# TCAN1146_PINOUT.net
KiCad netlist of a schematic drawn in Altium Designer
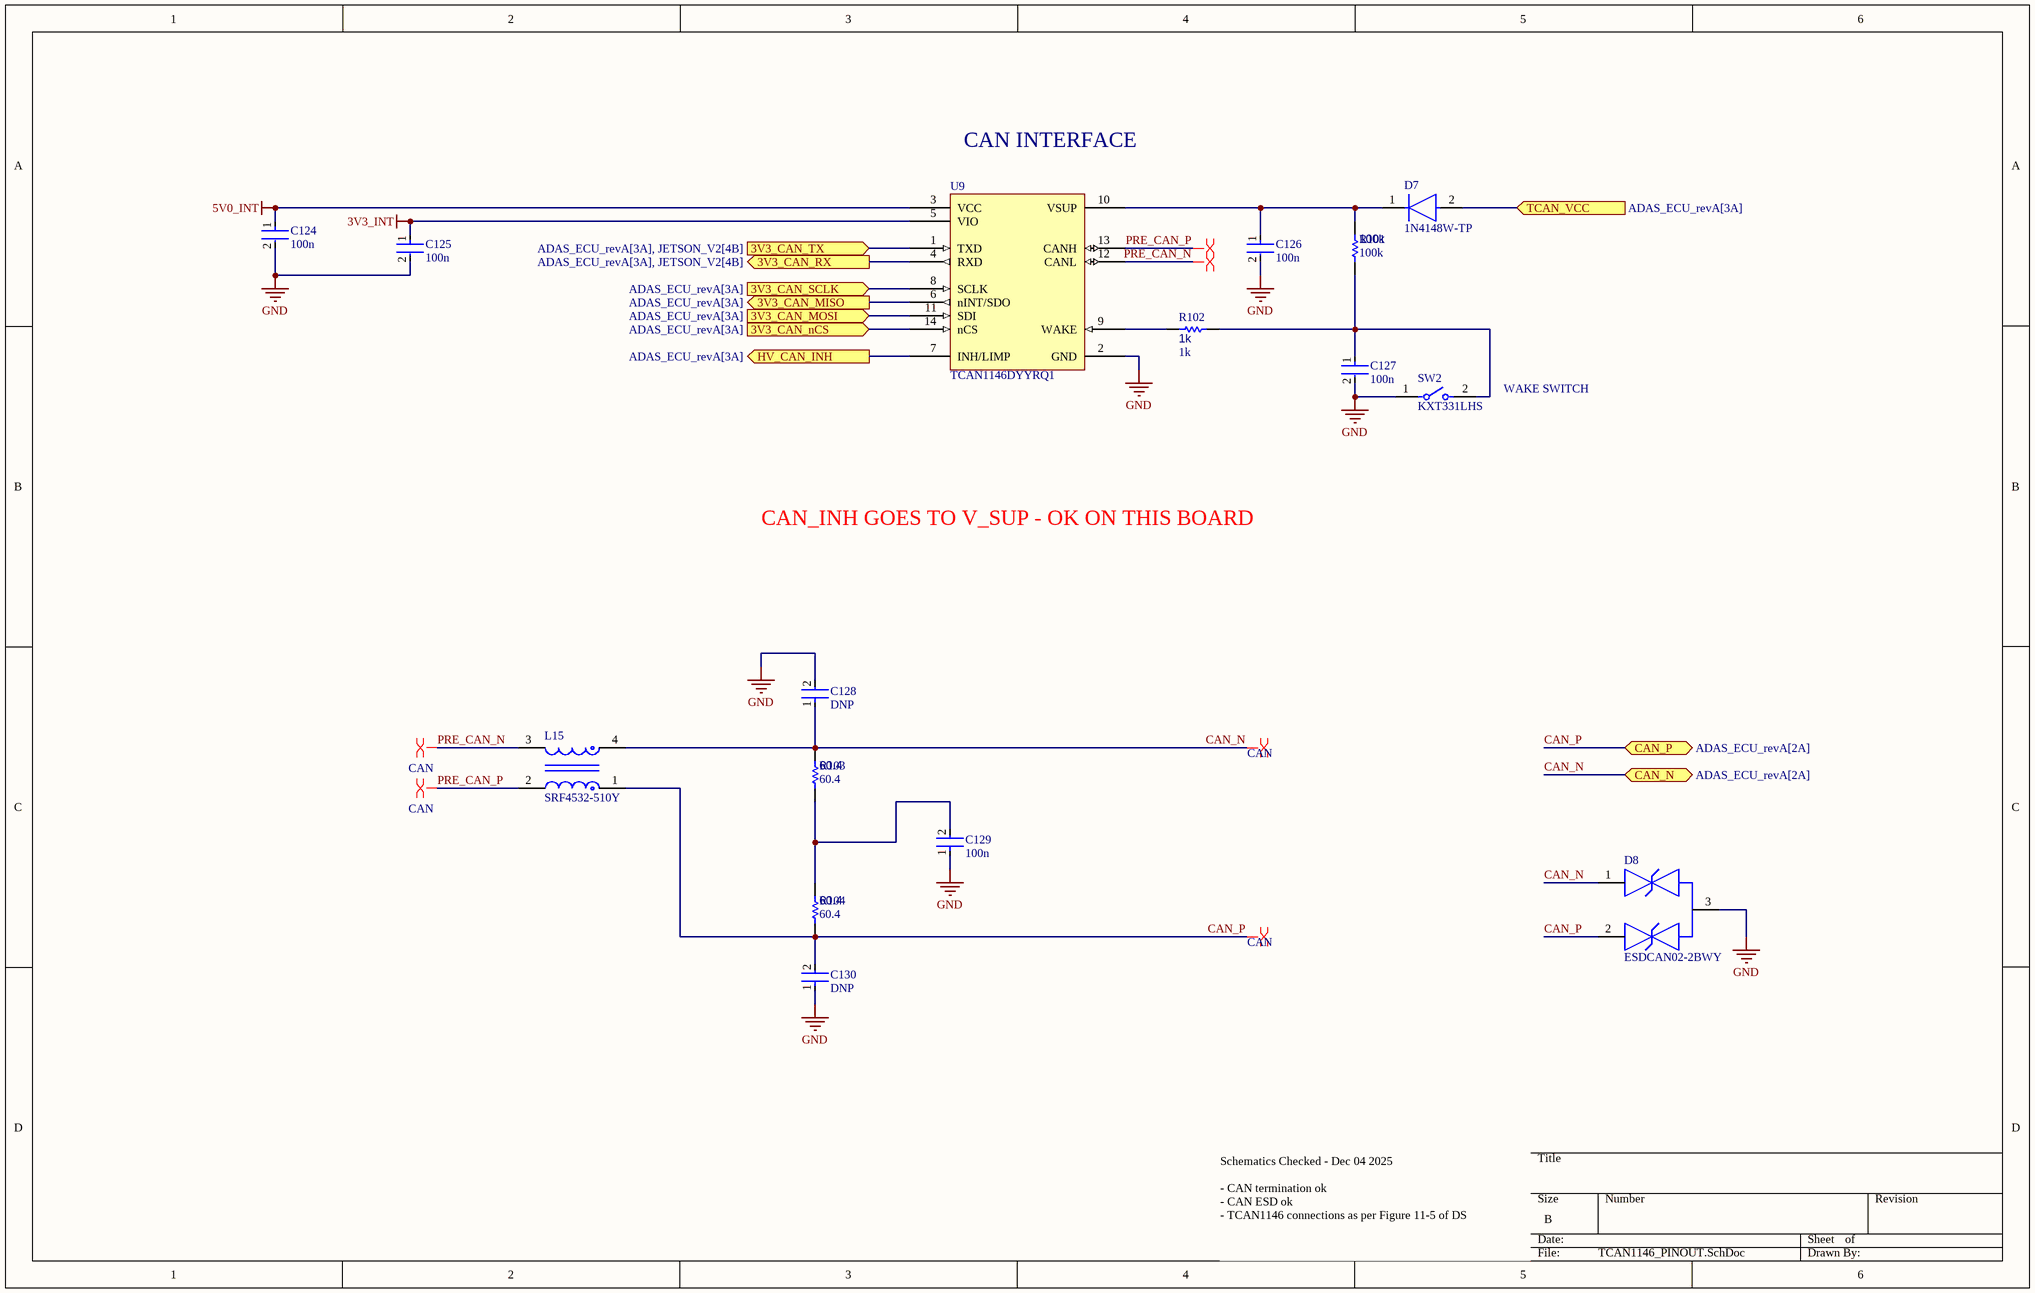
[diagram p0: TCAN1146_PINOUT.SchDoc]

(export (version "E")
  (design (tool "Eeschema 10.0.6"))
  (components
    (comp (ref "C124")
      (value "100n")
      (footprint "FP-0402-L_1_0_0_05-W_0_5-IPC_A")
      (description "LARGE PADS, 0402 CAP, CHANGE COMMENT TO MATCH REAL P/N")
      (libsource (lib "Space Concordia") (part "b4654b650e69147ec39a6b967a45e02"))
    )
    (comp (ref "C125")
      (value "100n")
      (footprint "FP-0402-L_1_0_0_05-W_0_5-IPC_A")
      (description "LARGE PADS, 0402 CAP, CHANGE COMMENT TO MATCH REAL P/N")
      (libsource (lib "Space Concordia") (part "b4654b650e69147ec39a6b967a45e02"))
    )
    (comp (ref "C126")
      (value "100n")
      (footprint "FP-0402-L_1_0_0_05-W_0_5-IPC_A")
      (description "LARGE PADS, 0402 CAP, CHANGE COMMENT TO MATCH REAL P/N")
      (libsource (lib "Space Concordia") (part "b4654b650e69147ec39a6b967a45e02"))
    )
    (comp (ref "C127")
      (value "100n")
      (footprint "FP-0402-L_1_0_0_05-W_0_5-IPC_A")
      (description "LARGE PADS, 0402 CAP, CHANGE COMMENT TO MATCH REAL P/N")
      (libsource (lib "Space Concordia") (part "b4654b650e69147ec39a6b967a45e02"))
    )
    (comp (ref "C128")
      (value "DNP")
      (footprint "FP-0402-L_1_0_0_05-W_0_5-IPC_A")
      (description "LARGE PADS, 0402 CAP, CHANGE COMMENT TO MATCH REAL P/N")
      (libsource (lib "Space Concordia") (part "b4654b650e69147ec39a6b967a45e02"))
    )
    (comp (ref "C129")
      (value "100n")
      (footprint "FP-0402-L_1_0_0_05-W_0_5-IPC_A")
      (description "LARGE PADS, 0402 CAP, CHANGE COMMENT TO MATCH REAL P/N")
      (libsource (lib "Space Concordia") (part "b4654b650e69147ec39a6b967a45e02"))
    )
    (comp (ref "C130")
      (value "DNP")
      (footprint "FP-0402-L_1_0_0_05-W_0_5-IPC_A")
      (description "LARGE PADS, 0402 CAP, CHANGE COMMENT TO MATCH REAL P/N")
      (libsource (lib "Space Concordia") (part "b4654b650e69147ec39a6b967a45e02"))
    )
    (comp (ref "D7")
      (value "1N4148W-TP")
      (footprint "FP-SOD-123-IPC_A")
      (description "DIODE GEN PURP 100V 150MA SOD123")
      (libsource (lib "Altium Content Vault") (part "d7152d700b627762746794eb795d46e"))
    )
    (comp (ref "D8")
      (value "ESDCAN02-2BWY")
      (footprint "FP-SOT323-3L-MFG")
      (description "TVS DIODE 26.5V 44V SOT323-3")
      (fields
        (field (name "MANUFACTURER") "STMicroelectronics")
        (field (name "OCTOPART") "https://octopart.com/esdcan02-2bwy-stmicroelectronics-58631133")
      )
      (libsource (lib "Altium Content Vault") (part "0b9019fb5e52ed66df21ec1535be59d"))
    )
    (comp (ref "L15")
      (value "SRF4532-510Y")
      (footprint "FP-SRF4532-MFG")
      (description "CMC 51UH 200MA 2LN 2KOHM SMD")
      (fields (field (name "TOLERANCE") "50%"))
      (libsource (lib "Altium Content Vault") (part "aca3f6a10b859f211cca95010157f3b"))
    )
    (comp (ref "R101")
      (value "100k")
      (footprint "R0603B")
      (description "Resistor")
      (fields (field (name "ALTIUM_VALUE") "100k"))
      (libsource (lib "Space Concordia") (part "Resistor"))
    )
    (comp (ref "R102")
      (value "1k")
      (footprint "R0603B")
      (description "Resistor")
      (fields (field (name "ALTIUM_VALUE") "1k"))
      (libsource (lib "Space Concordia") (part "Resistor"))
    )
    (comp (ref "R103")
      (value "60.4")
      (footprint "R0603B")
      (description "Resistor")
      (fields (field (name "ALTIUM_VALUE") "60.4"))
      (libsource (lib "Space Concordia") (part "Resistor"))
    )
    (comp (ref "R104")
      (value "60.4")
      (footprint "R0603B")
      (description "Resistor")
      (fields (field (name "ALTIUM_VALUE") "60.4"))
      (libsource (lib "Space Concordia") (part "Resistor"))
    )
    (comp (ref "SW2")
      (value "KXT331LHS")
      (footprint "FP-KXT331LHS-MFG")
      (description "SWITCH TACTILE SPST-NO 0.02A 15V")
      (libsource (lib "Altium Content Vault") (part "bb27bde45df87f1f469753f287ef5ae"))
    )
    (comp (ref "U9")
      (value "TCAN1146DYYRQ1")
      (footprint "TCAN1146DYYRQ1-Footprint-1")
      (libsource (lib "Space Concordia") (part "CMP-015-00012-2"))
    )
  )
  (nets
    (net (code "1") (name "/3V3_CAN_MISO") (class "Default")
      (node (ref "U9") (pin "6") (pinfunction "nINT/SDO_6") (pintype "output"))
    )
    (net (code "2") (name "/3V3_CAN_MOSI") (class "Default")
      (node (ref "U9") (pin "11") (pinfunction "SDI_11") (pintype "input"))
    )
    (net (code "3") (name "/3V3_CAN_RX") (class "Default")
      (node (ref "U9") (pin "4") (pinfunction "RXD_4") (pintype "output"))
    )
    (net (code "4") (name "/3V3_CAN_SCLK") (class "Default")
      (node (ref "U9") (pin "8") (pinfunction "SCLK_8") (pintype "input"))
    )
    (net (code "5") (name "/3V3_CAN_TX") (class "Default")
      (node (ref "U9") (pin "1") (pinfunction "TXD_1") (pintype "input"))
    )
    (net (code "6") (name "/3V3_CAN_nCS") (class "Default")
      (node (ref "U9") (pin "14") (pinfunction "nCS_14") (pintype "input"))
    )
    (net (code "7") (name "/CAN_N") (class "Default")
      (node (ref "C128") (pin "1") (pinfunction "1_1") (pintype "passive"))
      (node (ref "D8") (pin "1") (pinfunction "1_1") (pintype "passive"))
      (node (ref "L15") (pin "4") (pinfunction "4_4") (pintype "passive"))
      (node (ref "R103") (pin "2") (pinfunction "2_2") (pintype "passive"))
    )
    (net (code "8") (name "/CAN_P") (class "Default")
      (node (ref "C130") (pin "2") (pinfunction "2_2") (pintype "passive"))
      (node (ref "D8") (pin "2") (pinfunction "2_2") (pintype "passive"))
      (node (ref "L15") (pin "1") (pinfunction "1_1") (pintype "passive"))
      (node (ref "R104") (pin "1") (pinfunction "1_1") (pintype "passive"))
    )
    (net (code "9") (name "/HV_CAN_INH") (class "Default")
      (node (ref "U9") (pin "7") (pinfunction "INH/LIMP_7") (pintype "passive"))
    )
    (net (code "10") (name "/PRE_CAN_N") (class "Default")
      (node (ref "L15") (pin "3") (pinfunction "3_3") (pintype "passive"))
      (node (ref "U9") (pin "12") (pinfunction "CANL_12") (pintype "bidirectional"))
    )
    (net (code "11") (name "/PRE_CAN_P") (class "Default")
      (node (ref "L15") (pin "2") (pinfunction "2_2") (pintype "passive"))
      (node (ref "U9") (pin "13") (pinfunction "CANH_13") (pintype "bidirectional"))
    )
    (net (code "12") (name "/TCAN_VCC") (class "Default")
      (node (ref "D7") (pin "2") (pinfunction "A_2") (pintype "passive"))
    )
    (net (code "13") (name "3V3_INT") (class "Default")
      (node (ref "C125") (pin "1") (pinfunction "1_1") (pintype "passive"))
      (node (ref "U9") (pin "5") (pinfunction "VIO_5") (pintype "power_in"))
    )
    (net (code "14") (name "5V0_INT") (class "Default")
      (node (ref "C124") (pin "1") (pinfunction "1_1") (pintype "passive"))
      (node (ref "U9") (pin "3") (pinfunction "VCC_3") (pintype "power_in"))
    )
    (net (code "15") (name "GND") (class "Default")
      (node (ref "C124") (pin "2") (pinfunction "2_2") (pintype "passive"))
      (node (ref "C125") (pin "2") (pinfunction "2_2") (pintype "passive"))
      (node (ref "C126") (pin "2") (pinfunction "2_2") (pintype "passive"))
      (node (ref "C127") (pin "2") (pinfunction "2_2") (pintype "passive"))
      (node (ref "C128") (pin "2") (pinfunction "2_2") (pintype "passive"))
      (node (ref "C129") (pin "1") (pinfunction "1_1") (pintype "passive"))
      (node (ref "C130") (pin "1") (pinfunction "1_1") (pintype "passive"))
      (node (ref "D8") (pin "3") (pinfunction "3_3") (pintype "passive"))
      (node (ref "SW2") (pin "1") (pinfunction "1_1") (pintype "passive"))
      (node (ref "U9") (pin "2") (pinfunction "GND_2") (pintype "power_in"))
    )
    (net (code "16") (name "Net-(C127-Pad1)") (class "Default")
      (node (ref "C127") (pin "1") (pinfunction "1_1") (pintype "passive"))
      (node (ref "R101") (pin "1") (pinfunction "1_1") (pintype "passive"))
      (node (ref "R102") (pin "2") (pinfunction "2_2") (pintype "passive"))
      (node (ref "SW2") (pin "2") (pinfunction "2_2") (pintype "passive"))
    )
    (net (code "17") (name "Net-(C129-Pad2)") (class "Default")
      (node (ref "C129") (pin "2") (pinfunction "2_2") (pintype "passive"))
      (node (ref "R103") (pin "1") (pinfunction "1_1") (pintype "passive"))
      (node (ref "R104") (pin "2") (pinfunction "2_2") (pintype "passive"))
    )
    (net (code "18") (name "Net-(D7-C)") (class "Default")
      (node (ref "C126") (pin "1") (pinfunction "1_1") (pintype "passive"))
      (node (ref "D7") (pin "1") (pinfunction "C_1") (pintype "passive"))
      (node (ref "R101") (pin "2") (pinfunction "2_2") (pintype "passive"))
      (node (ref "U9") (pin "10") (pinfunction "VSUP_10") (pintype "power_in"))
    )
    (net (code "19") (name "Net-(U9-WAKE)") (class "Default")
      (node (ref "R102") (pin "1") (pinfunction "1_1") (pintype "passive"))
      (node (ref "U9") (pin "9") (pinfunction "WAKE_9") (pintype "input"))
    )
  )
)
